# Doorbellv1_3.net
KiCad netlist of a schematic drawn in Altium Designer
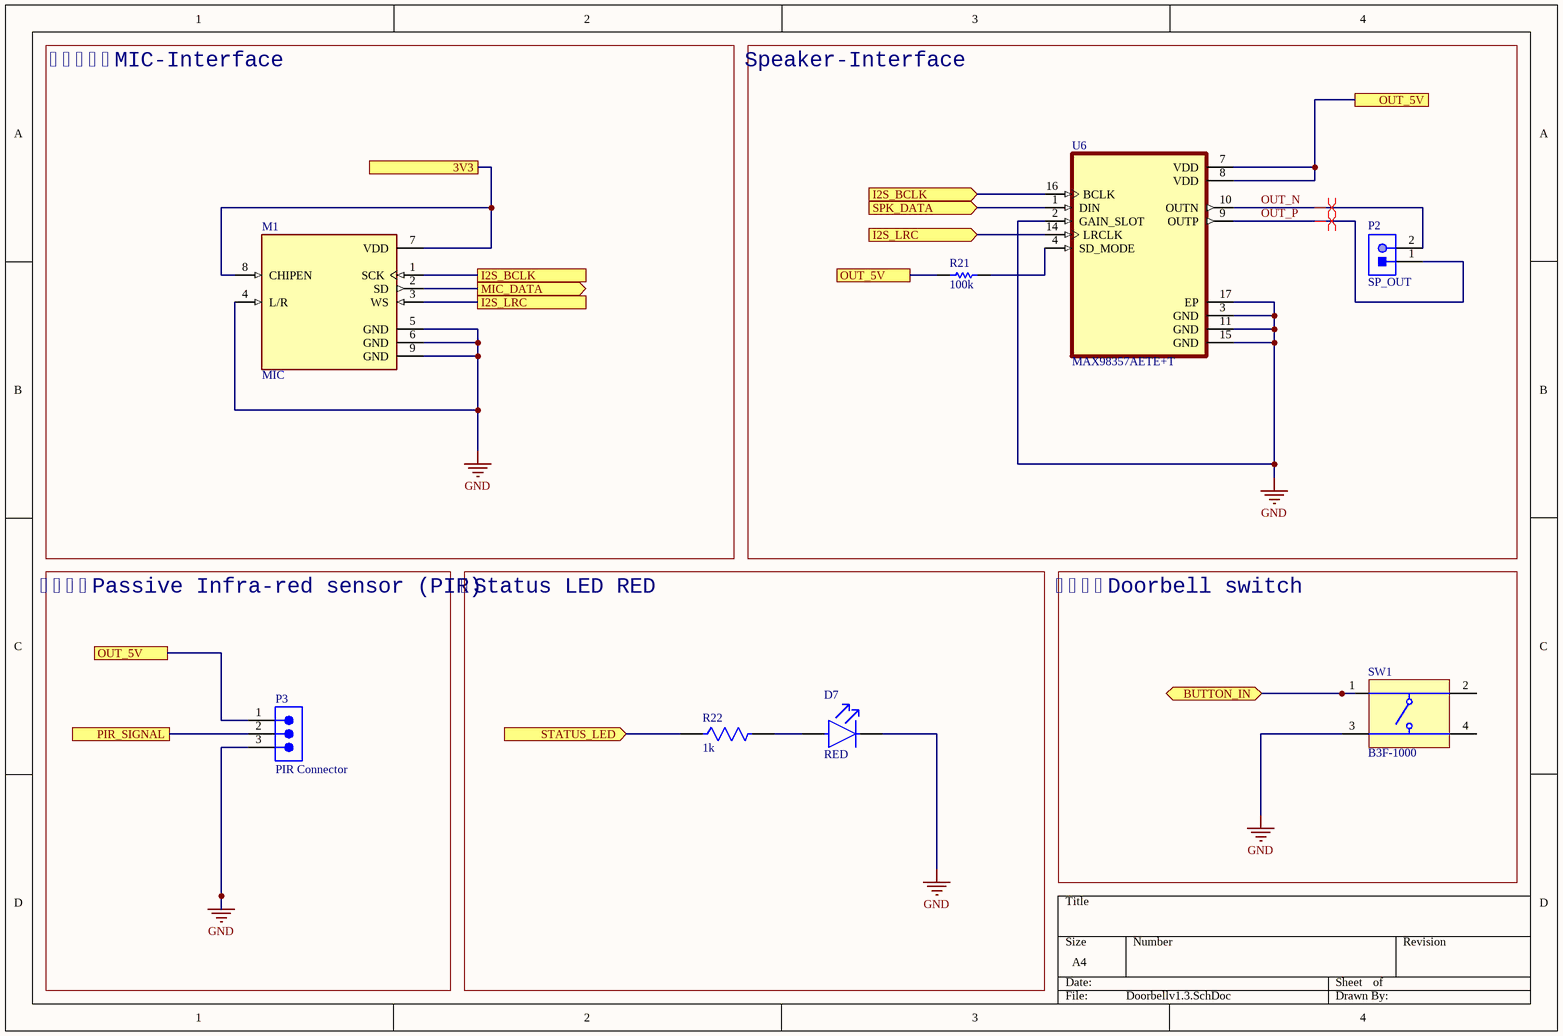
[diagram p0: Doorbellv1.3.SchDoc]

(export (version "E")
  (design (tool "Eeschema 10.0.6"))
  (components
    (comp (ref "D7")
      (value "RED")
      (footprint "FP-LS_R976-MFG")
      (description "LED RED DIFFUSED 0805 SMD")
      (libsource (lib "Altium Content Vault") (part "8706943c75ba83719d021d2fdc84c58"))
    )
    (comp (ref "M1")
      (value "MIC")
      (footprint "MIC_INMP441ACEZ-R7")
      (fields (field (name "MF") "TDK InvenSense") (field (name "MP") "INMP441ACEZ-R7"))
      (libsource (lib "INMP441ACEZ-R7 (1)") (part "INMP441ACEZ-R7"))
    )
    (comp (ref "P2")
      (value "SP_OUT")
      (footprint "JST-S2B-PH-K-S_V")
      (fields (field (name "TOLERANCE") "20%"))
      (libsource (lib "Altium Content Vault") (part "CN-1P-M-R2"))
    )
    (comp (ref "P3")
      (value "PIR Connector")
      (footprint "61300311121")
      (description "THT Vertical Pin Header WR-PHD, Pitch 2.54 mm, Single Row, 3 pins")
      (libsource (lib "Altium Content Vault") (part "Header_Male_1R_03P"))
    )
    (comp (ref "R21")
      (value "100k")
      (footprint "RESC0603(1608)_N")
      (description "100K 0.1W 1% 0603 (1608 Metric)  SMD")
      (fields (field (name "POWER") "0.1 W") (field (name "TOLERANCE") "1 %"))
      (libsource (lib "Altium Content Vault") (part "RES"))
    )
    (comp (ref "R22")
      (value "1k")
      (footprint "FP-MCU0805-IPC_A")
      (description "RES 1.05K OHM 0.5% 1/5W 0805")
      (fields (field (name "TOLERANCE") "0.1%"))
      (libsource (lib "Altium Content Vault") (part "1029c3af85768c4190bb7ad29bc67b5"))
    )
    (comp (ref "SW1")
      (value "B3F-1000")
      (footprint "OMRON-B3F-1000-4_V")
      (description "Tactile Switch, SPST-NO, 0.05 A, 5 to 24 V, -25 to 70 degC, 4-Pin THD, RoHS, Bulk")
      (libsource (lib "Altium Content Vault") (part "SW-SPST-4_A"))
    )
    (comp (ref "U6")
      (value "MAX98357AETE+T")
      (footprint "QFN50P300X300X80-17N")
      (description "Tiny, Low-Cost, PCM Class D Amplifier with Class AB Performance")
      (fields (field (name "MF") "Analog Devices"))
      (libsource (lib "MAX98357AETE_T") (part "MAX98357AETE+T"))
    )
  )
  (nets
    (net (code "1") (name "/3V3") (class "Default")
      (node (ref "M1") (pin "7") (pinfunction "VDD_7") (pintype "power_in"))
      (node (ref "M1") (pin "8") (pinfunction "CHIPEN_8") (pintype "input"))
    )
    (net (code "2") (name "/BUTTON_IN") (class "Default")
      (node (ref "SW1") (pin "1") (pinfunction "1_1") (pintype "passive"))
    )
    (net (code "3") (name "/I2S_BCLK") (class "Default")
      (node (ref "M1") (pin "1") (pinfunction "SCK_1") (pintype "input"))
      (node (ref "U6") (pin "16") (pinfunction "BCLK_16") (pintype "input"))
    )
    (net (code "4") (name "/I2S_LRC") (class "Default")
      (node (ref "M1") (pin "3") (pinfunction "WS_3") (pintype "input"))
      (node (ref "U6") (pin "14") (pinfunction "LRCLK_14") (pintype "input"))
    )
    (net (code "5") (name "/MIC_DATA") (class "Default")
      (node (ref "M1") (pin "2") (pinfunction "SD_2") (pintype "output"))
    )
    (net (code "6") (name "/OUT_5V") (class "Default")
      (node (ref "P3") (pin "1") (pinfunction "1_1") (pintype "passive"))
      (node (ref "R21") (pin "2") (pinfunction "2_2") (pintype "passive"))
      (node (ref "U6") (pin "7") (pinfunction "VDD_7") (pintype "power_in"))
      (node (ref "U6") (pin "8") (pinfunction "VDD_8") (pintype "power_in"))
    )
    (net (code "7") (name "/OUT_N") (class "Default")
      (node (ref "P2") (pin "2") (pinfunction "2_2") (pintype "passive"))
      (node (ref "U6") (pin "10") (pinfunction "OUTN_10") (pintype "output"))
    )
    (net (code "8") (name "/OUT_P") (class "Default")
      (node (ref "P2") (pin "1") (pinfunction "1_1") (pintype "passive"))
      (node (ref "U6") (pin "9") (pinfunction "OUTP_9") (pintype "output"))
    )
    (net (code "9") (name "/PIR_SIGNAL") (class "Default")
      (node (ref "P3") (pin "2") (pinfunction "2_2") (pintype "passive"))
    )
    (net (code "10") (name "/SPK_DATA") (class "Default")
      (node (ref "U6") (pin "1") (pinfunction "DIN_1") (pintype "input"))
    )
    (net (code "11") (name "/STATUS_LED") (class "Default")
      (node (ref "R22") (pin "1") (pinfunction "1_1") (pintype "passive"))
    )
    (net (code "12") (name "GND") (class "Default")
      (node (ref "D7") (pin "1") (pinfunction "C_1") (pintype "passive"))
      (node (ref "M1") (pin "4") (pinfunction "L/R_4") (pintype "input"))
      (node (ref "M1") (pin "5") (pinfunction "GND_5") (pintype "power_in"))
      (node (ref "M1") (pin "6") (pinfunction "GND_6") (pintype "power_in"))
      (node (ref "M1") (pin "9") (pinfunction "GND_9") (pintype "power_in"))
      (node (ref "P3") (pin "3") (pinfunction "3_3") (pintype "passive"))
      (node (ref "SW1") (pin "3") (pinfunction "3_3") (pintype "passive"))
      (node (ref "U6") (pin "11") (pinfunction "GND_11") (pintype "power_in"))
      (node (ref "U6") (pin "15") (pinfunction "GND_15") (pintype "power_in"))
      (node (ref "U6") (pin "17") (pinfunction "EP_17") (pintype "power_in"))
      (node (ref "U6") (pin "2") (pinfunction "GAIN_SLOT_2") (pintype "input"))
      (node (ref "U6") (pin "3") (pinfunction "GND_3") (pintype "power_in"))
    )
    (net (code "13") (name "Net-(D7-A)") (class "Default")
      (node (ref "D7") (pin "2") (pinfunction "A_2") (pintype "passive"))
      (node (ref "R22") (pin "2") (pinfunction "2_2") (pintype "passive"))
    )
    (net (code "14") (name "Net-(U6-SD_MODE)") (class "Default")
      (node (ref "R21") (pin "1") (pinfunction "1_1") (pintype "passive"))
      (node (ref "U6") (pin "4") (pinfunction "SD_MODE_4") (pintype "input"))
    )
    (net (code "15") (name "unconnected-(SW1-Pad2)") (class "Default")
      (node (ref "SW1") (pin "2") (pinfunction "2_2") (pintype "passive"))
    )
    (net (code "16") (name "unconnected-(SW1-Pad4)") (class "Default")
      (node (ref "SW1") (pin "4") (pinfunction "4_4") (pintype "passive"))
    )
  )
)
